# XBeeRadioMain.net
KiCad netlist of a schematic drawn in Altium Designer
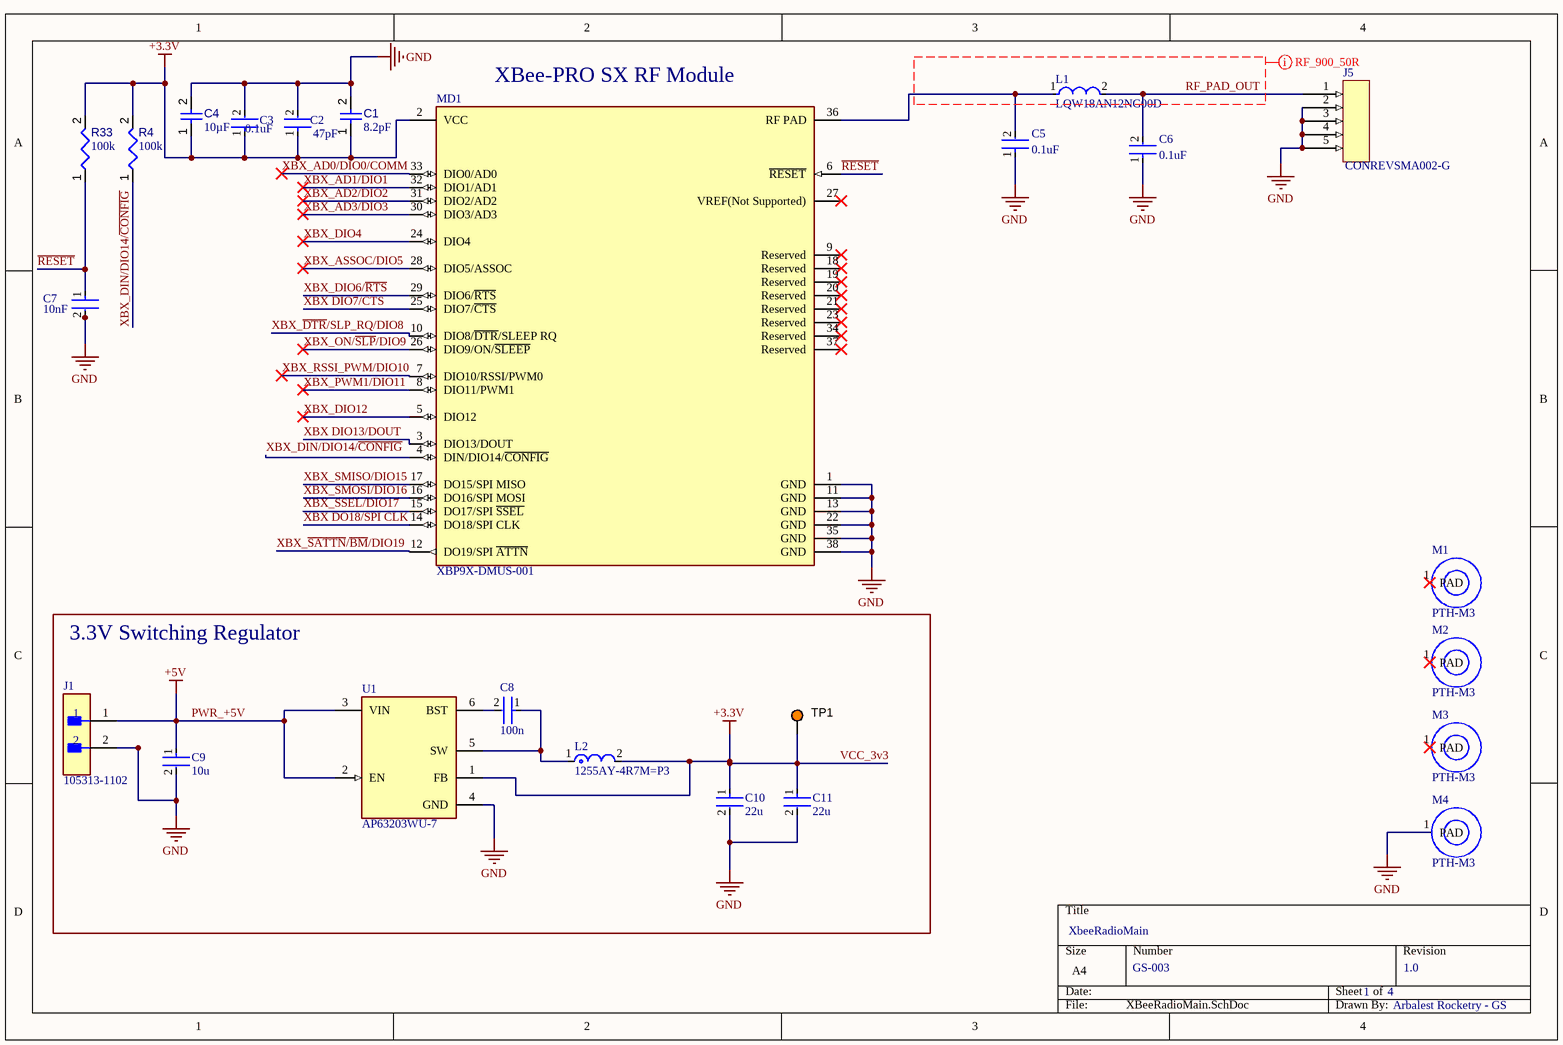
[diagram p0: XBeeRadioMain.SchDoc]

(export (version "E")
  (design (tool "Eeschema 10.0.6"))
  (components
    (comp (ref "C1")
      (value "8.2pF")
      (footprint "CAPC1608X06N")
      (fields (field (name "Comment") "600S8R2BT250XT4K"))
      (libsource (lib "York University") (part "CAP-NP-2"))
    )
    (comp (ref "C2")
      (value "47pF")
      (footprint "FP-C0805C470JDGACTU-MFG")
      (description "CAP CER 47PF 1KV C0G/NP0 0805")
      (fields (field (name "TOLERANCE") "5%"))
      (libsource (lib "Altium Content Vault") (part "02cd4be3c70576c341d710602a673aa"))
    )
    (comp (ref "C3")
      (value "0.1uF")
      (footprint "FP-C0603C-CF-MFG")
      (description "CAP CER 0.1UF 50V X7R 0603")
      (fields (field (name "TOLERANCE") "0.1") (field (name "MANUFACTURER") "KEMET"))
      (libsource (lib "Altium Content Vault") (part "b4654b650e69147ec39a6b967a45e02"))
    )
    (comp (ref "C4")
      (value "10µF")
      (footprint "CAPC0805(2012)145_L")
      (description "Chip Capacitor, 10µF +/-20%, 25V, 0805, Thickness 1.45 mm")
      (fields (field (name "TOLERANCE") "10%") (field (name "Comment") "Capacitor 10µF +/-20% 25V 0805"))
      (libsource (lib "York University") (part "CAP-NP-2"))
    )
    (comp (ref "C5")
      (value "0.1uF")
      (footprint "FP-C0603C-CF-MFG")
      (description "CAP CER 0.1UF 50V X7R 0603")
      (fields (field (name "TOLERANCE") "0.1") (field (name "MANUFACTURER") "KEMET"))
      (libsource (lib "Altium Content Vault") (part "b4654b650e69147ec39a6b967a45e02"))
    )
    (comp (ref "C6")
      (value "0.1uF")
      (footprint "FP-C0603C-CF-MFG")
      (description "CAP CER 0.1UF 50V X7R 0603")
      (fields (field (name "TOLERANCE") "0.1") (field (name "MANUFACTURER") "KEMET"))
      (libsource (lib "Altium Content Vault") (part "b4654b650e69147ec39a6b967a45e02"))
    )
    (comp (ref "C7")
      (value "10nF")
      (footprint "FP-C0603C-CF-MFG")
      (description "CAP CER 10000PF 50V X7R 0603")
      (fields
        (field (name "MANUFACTURER") "KEMET")
        (field (name "OCTOPART") "https://octopart.com/c0603c103k5ractu-kemet-133094")
      )
      (libsource (lib "Altium Content Vault") (part "b4654b650e69147ec39a6b967a45e02"))
    )
    (comp (ref "C8")
      (value "100n")
      (footprint "FP-0603-L_1_6_0_1-W_0_8_0-MFG")
      (description "None")
      (fields (field (name "TOLERANCE") "10%"))
      (libsource (lib "Altium Content Vault") (part "02cd4be3c70576c341d710602a673aa"))
    )
    (comp (ref "C9")
      (value "10u")
      (footprint "FP-GRM21B-0_2-e0_2_0_7-IPC_B")
      (description "Chip Multilayer Ceramic Capacitors for General Purpose, 0805, 10uF, X7R, 15%, 10%, 25V")
      (libsource (lib "Altium Content Vault") (part "b4654b650e69147ec39a6b967a45e02"))
    )
    (comp (ref "C10")
      (value "22u")
      (footprint "FP-1210-L_3_2_0_3-W_2_5_0-IPC_A")
      (description "None")
      (fields (field (name "TOLERANCE") "20%"))
      (libsource (lib "Altium Content Vault") (part "02cd4be3c70576c341d710602a673aa"))
    )
    (comp (ref "C11")
      (value "22u")
      (footprint "FP-1210-L_3_2_0_3-W_2_5_0-IPC_A")
      (description "None")
      (fields (field (name "TOLERANCE") "20%"))
      (libsource (lib "Altium Content Vault") (part "02cd4be3c70576c341d710602a673aa"))
    )
    (comp (ref "J1")
      (value "105313-1102")
      (footprint "FP-105313-1102-MFG")
      (description "CONN HEADER R/A 2POS 2.5MM")
      (libsource (lib "Altium Content Vault") (part "3bc925449376181038e59eaffc5286c"))
    )
    (comp (ref "J5")
      (value "CONREVSMA002-G")
      (footprint "CONREVSMA002-G-Footprint-1")
      (description "RF SMA Connector, Male, Board Mount, Solder Terminal")
      (libsource (lib "York University") (part "CONREVSMA002-G-Symbol-1"))
    )
    (comp (ref "L1")
      (value "LQW18AN12NG00D")
      (footprint "FP-LQW18AN_00-MFG")
      (description "Wire Wound RF Inductor 12nH ±2% 600mA 0.13Ω 0603 (1608)")
      (fields (field (name "TOLERANCE") "2%"))
      (libsource (lib "Altium Content Vault") (part "725321dda6339637d4d059423bc1c3c"))
    )
    (comp (ref "L2")
      (value "1255AY-4R7M=P3")
      (footprint "FP-DG6045C-MFG")
      (description "Shielded Wirewound Inductor 4.7uH 20% 4000mA 0.0276Ω SMD")
      (fields (field (name "TOLERANCE") "20%"))
      (libsource (lib "Altium Content Vault") (part "4cc4b267dca4c8e51f7102f422741d8"))
    )
    (comp (ref "M1")
      (value "PTH-M3")
      (footprint "PTH-M3-Footprint-1")
      (description "Mounting hole for M3 screw")
      (libsource (lib "York University") (part "PTH-M3"))
    )
    (comp (ref "M2")
      (value "PTH-M3")
      (footprint "PTH-M3-Footprint-1")
      (description "Mounting hole for M3 screw")
      (libsource (lib "York University") (part "PTH-M3"))
    )
    (comp (ref "M3")
      (value "PTH-M3")
      (footprint "PTH-M3-Footprint-1")
      (description "Mounting hole for M3 screw")
      (libsource (lib "York University") (part "PTH-M3"))
    )
    (comp (ref "M4")
      (value "PTH-M3")
      (footprint "PTH-M3-Footprint-1")
      (description "Mounting hole for M3 screw")
      (libsource (lib "York University") (part "PTH-M3"))
    )
    (comp (ref "MD1")
      (value "XBP9X-DMUS-001")
      (footprint "FP-XBP9X-DMUS-001-MFG")
      (description "XBEE PRO MOD TXRX ISM 915MHZ UFL")
      (fields
        (field (name "OCTOPART") "https://octopart.com/xbp9x-dmus-001-digi+international-71530758")
        (field (name "MANUFACTURER") "Digi International")
      )
      (libsource (lib "Altium Content Vault") (part "e92adbc7c680e86a0cddcc9352ac99f"))
    )
    (comp (ref "R4")
      (value "100k")
      (footprint "RESC2013X70X40ML20T20")
      (description "Chip Resistor, 100 KOhm, +/- 1%, 0.125 W, -55 to 155 degC, 0805 (2012 Metric)")
      (fields (field (name "POWER") "125mW") (field (name "TOLERANCE") "1%"))
      (libsource (lib "York University") (part "RES-2"))
    )
    (comp (ref "R33")
      (value "100k")
      (footprint "RESC2013X70X40ML20T20")
      (description "Chip Resistor, 100 KOhm, +/- 1%, 0.125 W, -55 to 155 degC, 0805 (2012 Metric)")
      (fields (field (name "POWER") "125mW") (field (name "TOLERANCE") "1%"))
      (libsource (lib "York University") (part "RES-2"))
    )
    (comp (ref "TP1")
      (value "3V3")
      (footprint "KSTN-5003")
      (description "Test Point, Orange, Height 4.6 mm, Tail Length 3 mm, 1-Pin THD, RoHS")
      (fields (field (name "MANUFACTURER") "Keystone"))
      (libsource (lib "York University") (part "TESTPOINT_ORANGE"))
    )
    (comp (ref "U1")
      (value "AP63203WU-7")
      (footprint "FP-TSOT26-MFG")
      (description "IC REG BUCK 3.3V 2A TSOT26")
      (fields
        (field (name "MANUFACTURER") "Diodes Inc.")
        (field (name "OCTOPART") "https://octopart.com/ap63203wu-7-diodes+inc.-98099550")
      )
      (libsource (lib "Altium Content Vault") (part "0e61c2974d7114b43f01ef96ae2e524"))
    )
  )
  (nets
    (net (code "1") (name "+3.3V") (class "Default")
      (node (ref "C1") (pin "1") (pinfunction "1_1") (pintype "passive"))
      (node (ref "C10") (pin "1") (pinfunction "1_1") (pintype "passive"))
      (node (ref "C11") (pin "1") (pinfunction "1_1") (pintype "passive"))
      (node (ref "C2") (pin "1") (pinfunction "1_1") (pintype "passive"))
      (node (ref "C3") (pin "1") (pinfunction "1_1") (pintype "passive"))
      (node (ref "C4") (pin "1") (pinfunction "1_1") (pintype "passive"))
      (node (ref "L2") (pin "2") (pinfunction "2_2") (pintype "passive"))
      (node (ref "MD1") (pin "2") (pinfunction "VCC_2") (pintype "power_in"))
      (node (ref "R33") (pin "2") (pinfunction "2_2") (pintype "passive"))
      (node (ref "R4") (pin "2") (pinfunction "2_2") (pintype "passive"))
      (node (ref "TP1") (pin "1") (pinfunction "1_1") (pintype "passive"))
      (node (ref "U1") (pin "1") (pinfunction "FB_1") (pintype "passive"))
    )
    (net (code "2") (name "+5V") (class "Default")
      (node (ref "C9") (pin "1") (pinfunction "1_1") (pintype "passive"))
      (node (ref "J1") (pin "1") (pinfunction "1_1") (pintype "passive"))
      (node (ref "U1") (pin "2") (pinfunction "EN_2") (pintype "input"))
      (node (ref "U1") (pin "3") (pinfunction "VIN_3") (pintype "power_in"))
    )
    (net (code "3") (name "/RF_PAD_OUT") (class "Default")
      (node (ref "C6") (pin "2") (pinfunction "2_2") (pintype "passive"))
      (node (ref "J5") (pin "1") (pintype "input"))
      (node (ref "L1") (pin "2") (pinfunction "2_2") (pintype "passive"))
    )
    (net (code "4") (name "/XBX DIO7{slash}~{CTS}") (class "Default")
      (node (ref "MD1") (pin "25") (pinfunction "DIO7/~{CTS}_25") (pintype "bidirectional"))
    )
    (net (code "5") (name "/XBX DIO13{slash}DOUT") (class "Default")
      (node (ref "MD1") (pin "3") (pinfunction "DIO13/DOUT_3") (pintype "bidirectional"))
    )
    (net (code "6") (name "/XBX DO18{slash}SPI CLK") (class "Default")
      (node (ref "MD1") (pin "14") (pinfunction "DO18/SPI_CLK_14") (pintype "bidirectional"))
    )
    (net (code "7") (name "/XBX_AD0{slash}DIO0{slash}COMM") (class "Default")
      (node (ref "MD1") (pin "33") (pinfunction "DIO0/AD0_33") (pintype "bidirectional+no_connect"))
    )
    (net (code "8") (name "/XBX_AD1{slash}DIO1") (class "Default")
      (node (ref "MD1") (pin "32") (pinfunction "DIO1/AD1_32") (pintype "bidirectional+no_connect"))
    )
    (net (code "9") (name "/XBX_AD2{slash}DIO2") (class "Default")
      (node (ref "MD1") (pin "31") (pinfunction "DIO2/AD2_31") (pintype "bidirectional+no_connect"))
    )
    (net (code "10") (name "/XBX_AD3{slash}DIO3") (class "Default")
      (node (ref "MD1") (pin "30") (pinfunction "DIO3/AD3_30") (pintype "bidirectional+no_connect"))
    )
    (net (code "11") (name "/XBX_ASSOC{slash}DIO5") (class "Default")
      (node (ref "MD1") (pin "28") (pinfunction "DIO5/ASSOC_28") (pintype "bidirectional+no_connect"))
    )
    (net (code "12") (name "/XBX_DIN{slash}DIO14{slash}~{CONFIG}") (class "Default")
      (node (ref "MD1") (pin "4") (pinfunction "DIN/DIO14/~{CONFIG}_4") (pintype "bidirectional"))
      (node (ref "R4") (pin "1") (pinfunction "1_1") (pintype "passive"))
    )
    (net (code "13") (name "/XBX_DIO4") (class "Default")
      (node (ref "MD1") (pin "24") (pinfunction "DIO4_24") (pintype "bidirectional+no_connect"))
    )
    (net (code "14") (name "/XBX_DIO6{slash}~{RTS}") (class "Default")
      (node (ref "MD1") (pin "29") (pinfunction "DIO6/~{RTS}_29") (pintype "bidirectional"))
    )
    (net (code "15") (name "/XBX_DIO12") (class "Default")
      (node (ref "MD1") (pin "5") (pinfunction "DIO12_5") (pintype "bidirectional+no_connect"))
    )
    (net (code "16") (name "/XBX_ON{slash}~{SLP}{slash}DIO9") (class "Default")
      (node (ref "MD1") (pin "26") (pinfunction "DIO9/ON/~{SLEEP}_26") (pintype "bidirectional+no_connect"))
    )
    (net (code "17") (name "/XBX_PWM1{slash}DIO11") (class "Default")
      (node (ref "MD1") (pin "8") (pinfunction "DIO11/PWM1_8") (pintype "bidirectional+no_connect"))
    )
    (net (code "18") (name "/XBX_RSSI_PWM{slash}DIO10") (class "Default")
      (node (ref "MD1") (pin "7") (pinfunction "DIO10/RSSI/PWM0_7") (pintype "bidirectional+no_connect"))
    )
    (net (code "19") (name "/XBX_SMISO{slash}DIO15") (class "Default")
      (node (ref "MD1") (pin "17") (pinfunction "DO15/SPI_MISO_17") (pintype "bidirectional"))
    )
    (net (code "20") (name "/XBX_SMOSI{slash}DIO16") (class "Default")
      (node (ref "MD1") (pin "16") (pinfunction "DO16/SPI_MOSI_16") (pintype "bidirectional"))
    )
    (net (code "21") (name "/XBX_~{DTR}{slash}SLP_RQ{slash}DIO8") (class "Default")
      (node (ref "MD1") (pin "10") (pinfunction "DIO8/~{DTR}/SLEEP_RQ_10") (pintype "bidirectional"))
    )
    (net (code "22") (name "/XBX_~{SATTN}{slash}~{BM}{slash}DIO19") (class "Default")
      (node (ref "MD1") (pin "12") (pinfunction "DO19/SPI_~{ATTN}_12") (pintype "output"))
    )
    (net (code "23") (name "/XBX_~{SSEL}{slash}DIO17") (class "Default")
      (node (ref "MD1") (pin "15") (pinfunction "DO17/SPI_~{SSEL}_15") (pintype "bidirectional"))
    )
    (net (code "24") (name "/~{RESET}") (class "Default")
      (node (ref "C7") (pin "1") (pinfunction "1_1") (pintype "passive"))
      (node (ref "MD1") (pin "6") (pinfunction "~{RESET}_6") (pintype "input"))
      (node (ref "R33") (pin "1") (pinfunction "1_1") (pintype "passive"))
    )
    (net (code "25") (name "GND") (class "Default")
      (node (ref "C1") (pin "2") (pinfunction "2_2") (pintype "passive"))
      (node (ref "C10") (pin "2") (pinfunction "2_2") (pintype "passive"))
      (node (ref "C11") (pin "2") (pinfunction "2_2") (pintype "passive"))
      (node (ref "C2") (pin "2") (pinfunction "2_2") (pintype "passive"))
      (node (ref "C3") (pin "2") (pinfunction "2_2") (pintype "passive"))
      (node (ref "C4") (pin "2") (pinfunction "2_2") (pintype "passive"))
      (node (ref "C5") (pin "1") (pinfunction "1_1") (pintype "passive"))
      (node (ref "C6") (pin "1") (pinfunction "1_1") (pintype "passive"))
      (node (ref "C7") (pin "2") (pinfunction "2_2") (pintype "passive"))
      (node (ref "C9") (pin "2") (pinfunction "2_2") (pintype "passive"))
      (node (ref "J1") (pin "2") (pinfunction "2_2") (pintype "passive"))
      (node (ref "J5") (pin "2") (pintype "input"))
      (node (ref "J5") (pin "3") (pintype "input"))
      (node (ref "J5") (pin "4") (pintype "input"))
      (node (ref "J5") (pin "5") (pintype "input"))
      (node (ref "M4") (pin "1") (pinfunction "PAD_1") (pintype "input"))
      (node (ref "MD1") (pin "1") (pinfunction "GND_1") (pintype "power_in"))
      (node (ref "MD1") (pin "11") (pinfunction "GND_11") (pintype "power_in"))
      (node (ref "MD1") (pin "13") (pinfunction "GND_13") (pintype "power_in"))
      (node (ref "MD1") (pin "22") (pinfunction "GND_22") (pintype "power_in"))
      (node (ref "MD1") (pin "35") (pinfunction "GND_35") (pintype "power_in"))
      (node (ref "MD1") (pin "38") (pinfunction "GND_38") (pintype "power_in"))
      (node (ref "U1") (pin "4") (pinfunction "GND_4") (pintype "power_in"))
    )
    (net (code "26") (name "Net-(MD1-RF_PAD)") (class "Default")
      (node (ref "C5") (pin "2") (pinfunction "2_2") (pintype "passive"))
      (node (ref "L1") (pin "1") (pinfunction "1_1") (pintype "passive"))
      (node (ref "MD1") (pin "36") (pinfunction "RF_PAD_36") (pintype "passive"))
    )
    (net (code "27") (name "Net-(U1-BST)") (class "Default")
      (node (ref "C8") (pin "2") (pinfunction "2_2") (pintype "passive"))
      (node (ref "U1") (pin "6") (pinfunction "BST_6") (pintype "passive"))
    )
    (net (code "28") (name "Net-(U1-SW)") (class "Default")
      (node (ref "C8") (pin "1") (pinfunction "1_1") (pintype "passive"))
      (node (ref "L2") (pin "1") (pinfunction "1_1") (pintype "passive"))
      (node (ref "U1") (pin "5") (pinfunction "SW_5") (pintype "passive"))
    )
    (net (code "29") (name "unconnected-(M1-PAD-Pad1)") (class "Default")
      (node (ref "M1") (pin "1") (pinfunction "PAD_1") (pintype "input+no_connect"))
    )
    (net (code "30") (name "unconnected-(M2-PAD-Pad1)") (class "Default")
      (node (ref "M2") (pin "1") (pinfunction "PAD_1") (pintype "input+no_connect"))
    )
    (net (code "31") (name "unconnected-(M3-PAD-Pad1)") (class "Default")
      (node (ref "M3") (pin "1") (pinfunction "PAD_1") (pintype "input+no_connect"))
    )
    (net (code "32") (name "unconnected-(MD1-Reserved-Pad9)") (class "Default")
      (node (ref "MD1") (pin "9") (pinfunction "Reserved_9") (pintype "passive+no_connect"))
    )
    (net (code "33") (name "unconnected-(MD1-Reserved-Pad18)") (class "Default")
      (node (ref "MD1") (pin "18") (pinfunction "Reserved_18") (pintype "passive+no_connect"))
    )
    (net (code "34") (name "unconnected-(MD1-Reserved-Pad19)") (class "Default")
      (node (ref "MD1") (pin "19") (pinfunction "Reserved_19") (pintype "passive+no_connect"))
    )
    (net (code "35") (name "unconnected-(MD1-Reserved-Pad20)") (class "Default")
      (node (ref "MD1") (pin "20") (pinfunction "Reserved_20") (pintype "passive+no_connect"))
    )
    (net (code "36") (name "unconnected-(MD1-Reserved-Pad21)") (class "Default")
      (node (ref "MD1") (pin "21") (pinfunction "Reserved_21") (pintype "passive+no_connect"))
    )
    (net (code "37") (name "unconnected-(MD1-Reserved-Pad23)") (class "Default")
      (node (ref "MD1") (pin "23") (pinfunction "Reserved_23") (pintype "passive+no_connect"))
    )
    (net (code "38") (name "unconnected-(MD1-Reserved-Pad34)") (class "Default")
      (node (ref "MD1") (pin "34") (pinfunction "Reserved_34") (pintype "passive+no_connect"))
    )
    (net (code "39") (name "unconnected-(MD1-Reserved-Pad37)") (class "Default")
      (node (ref "MD1") (pin "37") (pinfunction "Reserved_37") (pintype "passive+no_connect"))
    )
    (net (code "40") (name "unconnected-(MD1-VREF(Not_Supported)-Pad27)") (class "Default")
      (node (ref "MD1") (pin "27") (pinfunction "VREF(Not_Supported)_27") (pintype "passive+no_connect"))
    )
  )
)
